# USART_IrDA.net
KiCad netlist of a schematic drawn in Altium Designer
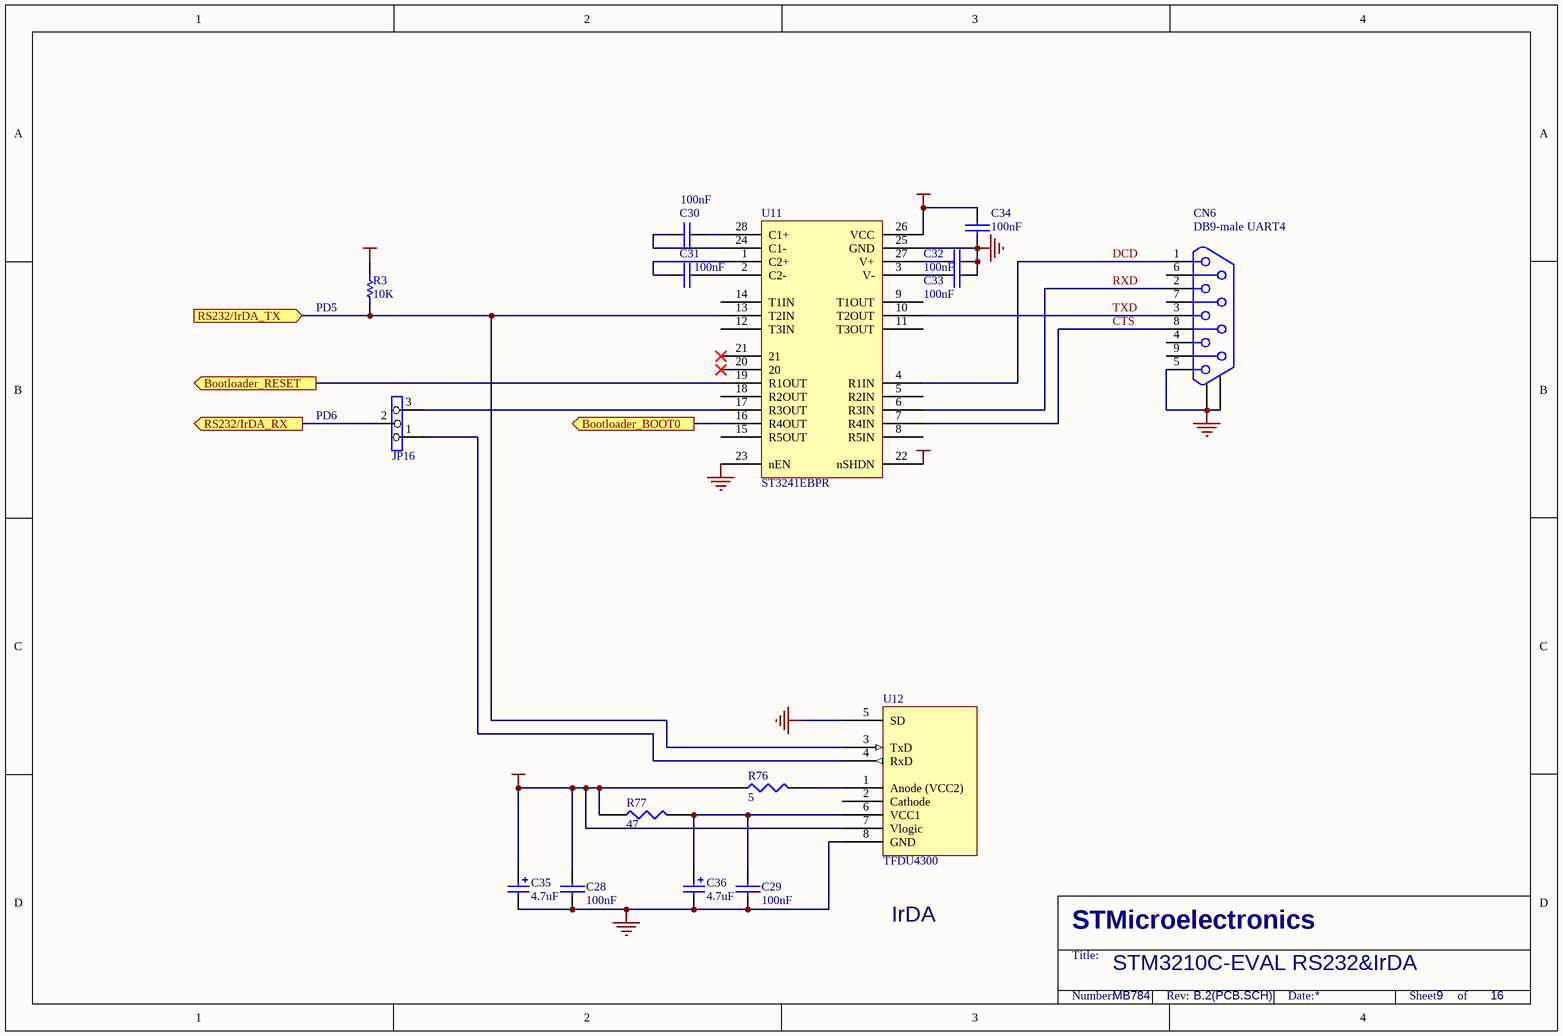
[diagram p0: USART&IrDA.SchDoc]

(export (version "E")
  (design (tool "Eeschema 10.0.6"))
  (components
    (comp (ref "C28")
      (value "100nF")
      (footprint "0603C")
      (description "Capacitor")
      (libsource (lib "*") (part "CAP"))
    )
    (comp (ref "C29")
      (value "100nF")
      (footprint "0603C")
      (description "Capacitor")
      (libsource (lib "*") (part "CAP"))
    )
    (comp (ref "C30")
      (value "100nF")
      (footprint "0603C")
      (description "Capacitor")
      (libsource (lib "*") (part "CAP"))
    )
    (comp (ref "C31")
      (value "100nF")
      (footprint "0603C")
      (description "Capacitor")
      (libsource (lib "*") (part "CAP"))
    )
    (comp (ref "C32")
      (value "100nF")
      (footprint "0603C")
      (description "Capacitor")
      (libsource (lib "*") (part "CAP"))
    )
    (comp (ref "C33")
      (value "100nF")
      (footprint "0603C")
      (description "Capacitor")
      (libsource (lib "*") (part "CAP"))
    )
    (comp (ref "C34")
      (value "100nF")
      (footprint "0603C")
      (description "Capacitor")
      (libsource (lib "*") (part "CAP"))
    )
    (comp (ref "C35")
      (value "4.7uF")
      (footprint "TAN-A")
      (description "Polarized Capacitor (Radial)")
      (fields (field (name "PUBLISHER") "Altium Limited"))
      (libsource (lib "Miscellaneous Devices") (part "Cap Pol1"))
    )
    (comp (ref "C36")
      (value "4.7uF")
      (footprint "TAN-A")
      (description "Polarized Capacitor (Radial)")
      (fields (field (name "PUBLISHER") "Altium Limited"))
      (libsource (lib "Miscellaneous Devices") (part "Cap Pol1"))
    )
    (comp (ref "CN6") (value "DB9-male UART4") (footprint "DB9/M") (libsource (lib "*") (part "DB9")))
    (comp (ref "JP16") (value "~") (footprint "SIP3") (libsource (lib "STR910_SCHLIB") (part "Jumper3")))
    (comp (ref "R3")
      (value "10K")
      (footprint "0603R")
      (description "Resistor")
      (fields (field (name "PUBLISHER") "Altium Limited"))
      (libsource (lib "Miscellaneous Devices") (part "Res1"))
    )
    (comp (ref "R76") (value "5") (footprint "0603R") (libsource (lib "*") (part "RES1")))
    (comp (ref "R77") (value "47") (footprint "0603R") (libsource (lib "*") (part "RES1")))
    (comp (ref "U11") (value "ST3241EBPR") (footprint "SSOP28") (libsource (lib "*") (part "ST3241")))
    (comp (ref "U12") (value "TFDU4300") (footprint "IR_VISHAY3") (libsource (lib "*") (part "TFDU4300")))
  )
  (nets
    (net (code "1") (name "+3V3") (class "Default")
      (node (ref "C28") (pin "1") (pinfunction "1_1") (pintype "passive"))
      (node (ref "C34") (pin "2") (pinfunction "2_2") (pintype "passive"))
      (node (ref "C35") (pin "1") (pinfunction "1_1") (pintype "passive"))
      (node (ref "R3") (pin "1") (pinfunction "1_1") (pintype "passive"))
      (node (ref "R76") (pin "1") (pinfunction "1_1") (pintype "passive"))
      (node (ref "R77") (pin "1") (pinfunction "1_1") (pintype "passive"))
      (node (ref "U11") (pin "22") (pinfunction "nSHDN_22") (pintype "passive"))
      (node (ref "U11") (pin "26") (pinfunction "VCC_26") (pintype "passive"))
      (node (ref "U12") (pin "7") (pinfunction "Vlogic_7") (pintype "passive"))
    )
    (net (code "2") (name "/Bootloader_BOOT0") (class "Default")
      (node (ref "U11") (pin "16") (pinfunction "R4OUT_16") (pintype "passive"))
    )
    (net (code "3") (name "/Bootloader_RESET") (class "Default")
      (node (ref "U11") (pin "19") (pinfunction "R1OUT_19") (pintype "passive"))
    )
    (net (code "4") (name "/CTS") (class "Default")
      (node (ref "CN6") (pin "8") (pinfunction "8_8") (pintype "passive"))
      (node (ref "U11") (pin "7") (pinfunction "R4IN_7") (pintype "passive"))
    )
    (net (code "5") (name "/DCD") (class "Default")
      (node (ref "CN6") (pin "1") (pinfunction "1_1") (pintype "passive"))
      (node (ref "U11") (pin "4") (pinfunction "R1IN_4") (pintype "passive"))
    )
    (net (code "6") (name "/RS232{slash}IrDA_RX") (class "Default")
      (node (ref "JP16") (pin "2") (pintype "passive"))
    )
    (net (code "7") (name "/RS232{slash}IrDA_TX") (class "Default")
      (node (ref "R3") (pin "2") (pinfunction "2_2") (pintype "passive"))
      (node (ref "U11") (pin "13") (pinfunction "T2IN_13") (pintype "passive"))
      (node (ref "U12") (pin "3") (pinfunction "TxD_3") (pintype "input"))
    )
    (net (code "8") (name "/RXD") (class "Default")
      (node (ref "CN6") (pin "2") (pinfunction "2_2") (pintype "passive"))
      (node (ref "U11") (pin "6") (pinfunction "R3IN_6") (pintype "passive"))
    )
    (net (code "9") (name "/TXD") (class "Default")
      (node (ref "CN6") (pin "3") (pinfunction "3_3") (pintype "passive"))
      (node (ref "U11") (pin "10") (pinfunction "T2OUT_10") (pintype "passive"))
    )
    (net (code "10") (name "GND") (class "Default")
      (node (ref "C28") (pin "2") (pinfunction "2_2") (pintype "passive"))
      (node (ref "C29") (pin "2") (pinfunction "2_2") (pintype "passive"))
      (node (ref "C32") (pin "2") (pinfunction "2_2") (pintype "passive"))
      (node (ref "C33") (pin "2") (pinfunction "2_2") (pintype "passive"))
      (node (ref "C34") (pin "1") (pinfunction "1_1") (pintype "passive"))
      (node (ref "C35") (pin "2") (pinfunction "2_2") (pintype "passive"))
      (node (ref "C36") (pin "2") (pinfunction "2_2") (pintype "passive"))
      (node (ref "CN6") (pin "0") (pinfunction "0_0") (pintype "passive"))
      (node (ref "CN6") (pin "5") (pinfunction "5_5") (pintype "passive"))
      (node (ref "U11") (pin "23") (pinfunction "nEN_23") (pintype "passive"))
      (node (ref "U11") (pin "25") (pinfunction "GND_25") (pintype "passive"))
      (node (ref "U12") (pin "5") (pinfunction "SD_5") (pintype "passive"))
      (node (ref "U12") (pin "8") (pinfunction "GND_8") (pintype "passive"))
    )
    (net (code "11") (name "Net-(U11-C1+)") (class "Default")
      (node (ref "C30") (pin "2") (pinfunction "2_2") (pintype "passive"))
      (node (ref "U11") (pin "28") (pinfunction "C1+_28") (pintype "passive"))
    )
    (net (code "12") (name "Net-(U11-C1-)") (class "Default")
      (node (ref "C30") (pin "1") (pinfunction "1_1") (pintype "passive"))
      (node (ref "U11") (pin "24") (pinfunction "C1-_24") (pintype "passive"))
    )
    (net (code "13") (name "Net-(U11-C2+)") (class "Default")
      (node (ref "C31") (pin "1") (pinfunction "1_1") (pintype "passive"))
      (node (ref "U11") (pin "1") (pinfunction "C2+_1") (pintype "passive"))
    )
    (net (code "14") (name "Net-(U11-C2-)") (class "Default")
      (node (ref "C31") (pin "2") (pinfunction "2_2") (pintype "passive"))
      (node (ref "U11") (pin "2") (pinfunction "C2-_2") (pintype "passive"))
    )
    (net (code "15") (name "Net-(U11-R3OUT)") (class "Default")
      (node (ref "JP16") (pin "3") (pintype "passive"))
      (node (ref "U11") (pin "17") (pinfunction "R3OUT_17") (pintype "passive"))
    )
    (net (code "16") (name "Net-(U11-V+)") (class "Default")
      (node (ref "C32") (pin "1") (pinfunction "1_1") (pintype "passive"))
      (node (ref "U11") (pin "27") (pinfunction "V+_27") (pintype "passive"))
    )
    (net (code "17") (name "Net-(U11-V-)") (class "Default")
      (node (ref "C33") (pin "1") (pinfunction "1_1") (pintype "passive"))
      (node (ref "U11") (pin "3") (pinfunction "V-_3") (pintype "passive"))
    )
    (net (code "18") (name "Net-(U12-Anode_(VCC2))") (class "Default")
      (node (ref "R76") (pin "2") (pinfunction "2_2") (pintype "passive"))
      (node (ref "U12") (pin "1") (pinfunction "Anode_(VCC2)_1") (pintype "passive"))
    )
    (net (code "19") (name "Net-(U12-RxD)") (class "Default")
      (node (ref "JP16") (pin "1") (pintype "passive"))
      (node (ref "U12") (pin "4") (pinfunction "RxD_4") (pintype "output"))
    )
    (net (code "20") (name "Net-(U12-VCC1)") (class "Default")
      (node (ref "C29") (pin "1") (pinfunction "1_1") (pintype "passive"))
      (node (ref "C36") (pin "1") (pinfunction "1_1") (pintype "passive"))
      (node (ref "R77") (pin "2") (pinfunction "2_2") (pintype "passive"))
      (node (ref "U12") (pin "6") (pinfunction "VCC1_6") (pintype "passive"))
    )
    (net (code "21") (name "unconnected-(CN6-Pad4)") (class "Default")
      (node (ref "CN6") (pin "4") (pinfunction "4_4") (pintype "passive"))
    )
    (net (code "22") (name "unconnected-(CN6-Pad6)") (class "Default")
      (node (ref "CN6") (pin "6") (pinfunction "6_6") (pintype "passive"))
    )
    (net (code "23") (name "unconnected-(CN6-Pad7)") (class "Default")
      (node (ref "CN6") (pin "7") (pinfunction "7_7") (pintype "passive"))
    )
    (net (code "24") (name "unconnected-(CN6-Pad9)") (class "Default")
      (node (ref "CN6") (pin "9") (pinfunction "9_9") (pintype "passive"))
    )
    (net (code "25") (name "unconnected-(U11-Pad20)") (class "Default")
      (node (ref "U11") (pin "20") (pinfunction "20_20") (pintype "passive+no_connect"))
    )
    (net (code "26") (name "unconnected-(U11-Pad21)") (class "Default")
      (node (ref "U11") (pin "21") (pinfunction "21_21") (pintype "passive+no_connect"))
    )
    (net (code "27") (name "unconnected-(U11-R2IN-Pad5)") (class "Default")
      (node (ref "U11") (pin "5") (pinfunction "R2IN_5") (pintype "passive"))
    )
    (net (code "28") (name "unconnected-(U11-R2OUT-Pad18)") (class "Default")
      (node (ref "U11") (pin "18") (pinfunction "R2OUT_18") (pintype "passive"))
    )
    (net (code "29") (name "unconnected-(U11-R5IN-Pad8)") (class "Default")
      (node (ref "U11") (pin "8") (pinfunction "R5IN_8") (pintype "passive"))
    )
    (net (code "30") (name "unconnected-(U11-R5OUT-Pad15)") (class "Default")
      (node (ref "U11") (pin "15") (pinfunction "R5OUT_15") (pintype "passive"))
    )
    (net (code "31") (name "unconnected-(U11-T1IN-Pad14)") (class "Default")
      (node (ref "U11") (pin "14") (pinfunction "T1IN_14") (pintype "passive"))
    )
    (net (code "32") (name "unconnected-(U11-T1OUT-Pad9)") (class "Default")
      (node (ref "U11") (pin "9") (pinfunction "T1OUT_9") (pintype "passive"))
    )
    (net (code "33") (name "unconnected-(U11-T3IN-Pad12)") (class "Default")
      (node (ref "U11") (pin "12") (pinfunction "T3IN_12") (pintype "passive"))
    )
    (net (code "34") (name "unconnected-(U11-T3OUT-Pad11)") (class "Default")
      (node (ref "U11") (pin "11") (pinfunction "T3OUT_11") (pintype "passive"))
    )
    (net (code "35") (name "unconnected-(U12-Cathode-Pad2)") (class "Default")
      (node (ref "U12") (pin "2") (pinfunction "Cathode_2") (pintype "passive"))
    )
  )
)
